# 01_detection.net
KiCad netlist of a schematic drawn in Altium Designer
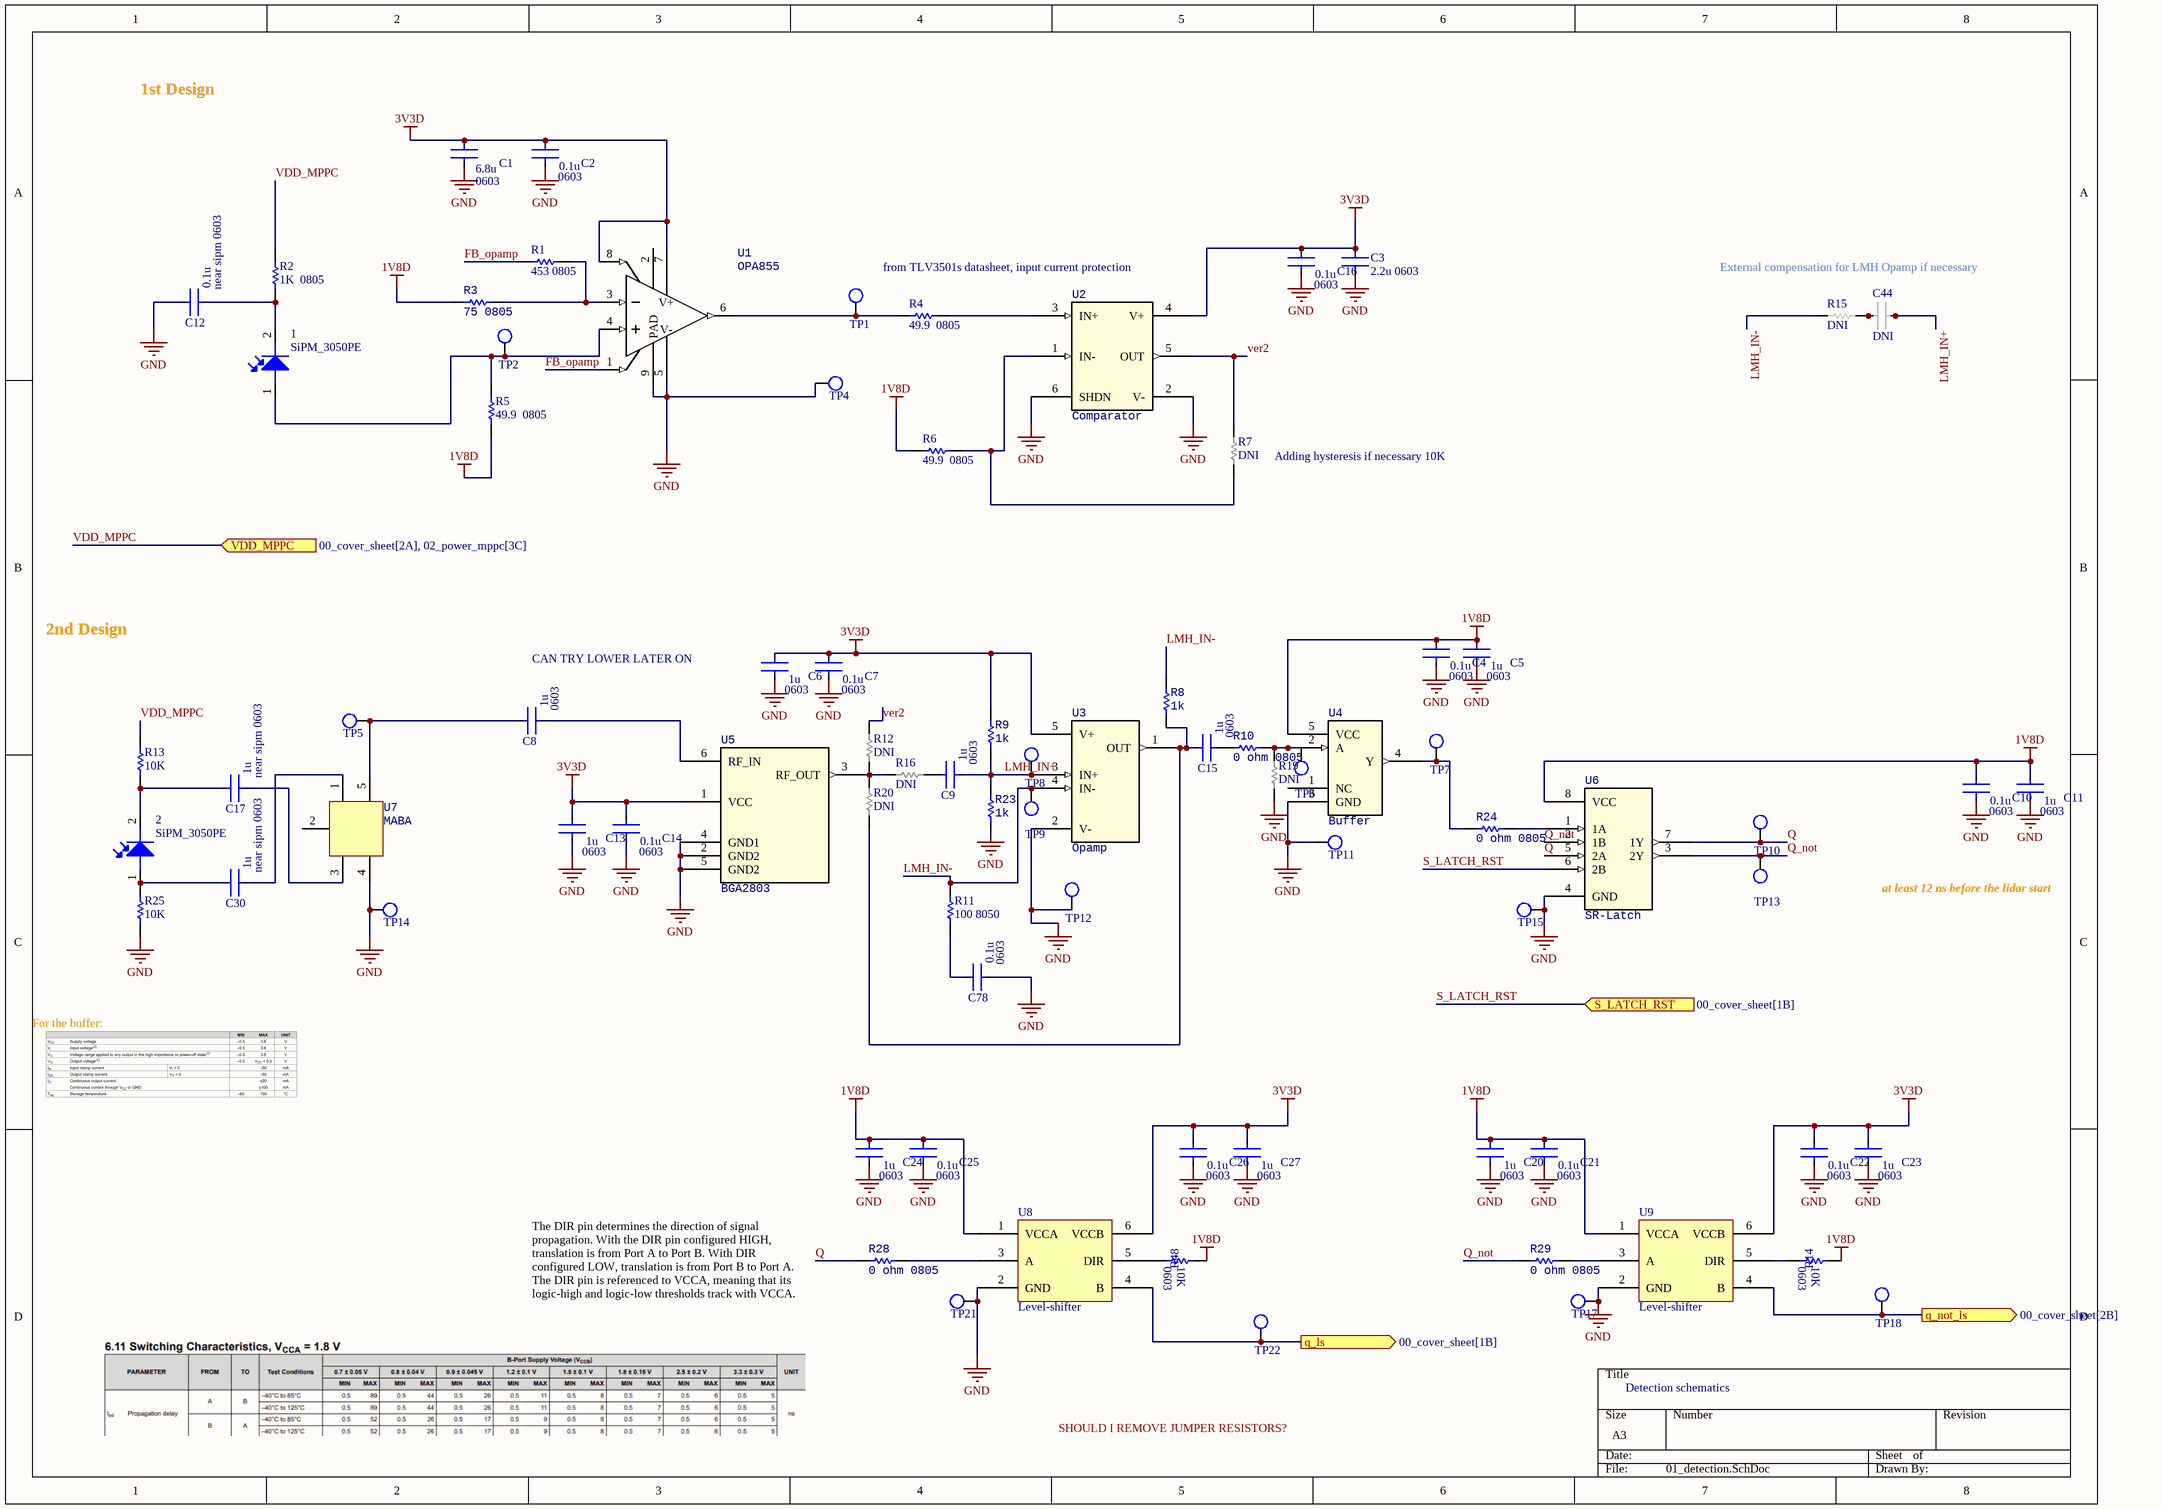
[diagram p0: 01_detection.SchDoc]

(export (version "E")
  (design (tool "Eeschema 10.0.6"))
  (components
    (comp (ref "1")
      (value "SiPM_3050PE")
      (footprint "MPPC-S13360-3050PE")
      (libsource (lib "tcspc00") (part "SiPM_3050PE"))
    )
    (comp (ref "2")
      (value "SiPM_3050PE")
      (footprint "MPPC-S13360-3050PE")
      (libsource (lib "tcspc00") (part "SiPM_3050PE"))
    )
    (comp (ref "C1")
      (value "C1608X5R1E685K080AC")
      (footprint "CAPTDK0603")
      (description "CAP CER 6.8UF 25V X5R 0603")
      (libsource (lib "tcspc00") (part "C1608X5R1E685K080AC"))
    )
    (comp (ref "C2")
      (value "CGA3E2X7R1H104K080AA")
      (footprint "CAPTDK0603")
      (description "CAP CER 0.1UF 50V X7R 0603")
      (libsource (lib "tcspc00") (part "CGA3E2X7R1H104K080AA"))
    )
    (comp (ref "C3")
      (value "2.2u 0603")
      (footprint "CAPTDK0603")
      (description "CAP CER 2.2UF 25V X5R 0603")
      (libsource (lib "tcspc00") (part "C1608X5R1E225K080AB"))
    )
    (comp (ref "C4")
      (value "CGA3E2X7R1H104K080AA")
      (footprint "CAPTDK0603")
      (description "CAP CER 0.1UF 50V X7R 0603")
      (libsource (lib "tcspc00") (part "CGA3E2X7R1H104K080AA"))
    )
    (comp (ref "C5")
      (value "C1608X5R1E105K080AC")
      (footprint "CAPTDK0603")
      (description "CAP CER 1UF 25V X5R 0603")
      (libsource (lib "tcspc00") (part "C1608X5R1E105K080AC"))
    )
    (comp (ref "C6")
      (value "C1608X5R1E105K080AC")
      (footprint "CAPTDK0603")
      (description "CAP CER 1UF 25V X5R 0603")
      (libsource (lib "tcspc00") (part "C1608X5R1E105K080AC"))
    )
    (comp (ref "C7")
      (value "CGA3E2X7R1H104K080AA")
      (footprint "CAPTDK0603")
      (description "CAP CER 0.1UF 50V X7R 0603")
      (libsource (lib "tcspc00") (part "CGA3E2X7R1H104K080AA"))
    )
    (comp (ref "C8")
      (value "C1608X5R1E105K080AC")
      (footprint "CAPTDK0603")
      (description "CAP CER 1UF 25V X5R 0603")
      (libsource (lib "tcspc00") (part "C1608X5R1E105K080AC"))
    )
    (comp (ref "C9")
      (value "C1608X5R1E105K080AC")
      (footprint "CAPTDK0603")
      (description "CAP CER 1UF 25V X5R 0603")
      (libsource (lib "tcspc00") (part "C1608X5R1E105K080AC"))
    )
    (comp (ref "C10")
      (value "CGA3E2X7R1H104K080AA")
      (footprint "CAPTDK0603")
      (description "CAP CER 0.1UF 50V X7R 0603")
      (libsource (lib "tcspc00") (part "CGA3E2X7R1H104K080AA"))
    )
    (comp (ref "C11")
      (value "C1608X5R1E105K080AC")
      (footprint "CAPTDK0603")
      (description "CAP CER 1UF 25V X5R 0603")
      (libsource (lib "tcspc00") (part "C1608X5R1E105K080AC"))
    )
    (comp (ref "C12")
      (value "CL10B104KC8NNNC")
      (footprint "CAPTDK0603")
      (description "CAP CER 0.1UF 100V X7R 0603")
      (libsource (lib "tcspc00") (part "CL10B104KC8NNNC"))
    )
    (comp (ref "C13")
      (value "C1608X5R1E105K080AC")
      (footprint "CAPTDK0603")
      (description "CAP CER 1UF 25V X5R 0603")
      (libsource (lib "tcspc00") (part "C1608X5R1E105K080AC"))
    )
    (comp (ref "C14")
      (value "CGA3E2X7R1H104K080AA")
      (footprint "CAPTDK0603")
      (description "CAP CER 0.1UF 50V X7R 0603")
      (libsource (lib "tcspc00") (part "CGA3E2X7R1H104K080AA"))
    )
    (comp (ref "C15")
      (value "C1608X5R1E105K080AC")
      (footprint "CAPTDK0603")
      (description "CAP CER 1UF 25V X5R 0603")
      (libsource (lib "tcspc00") (part "C1608X5R1E105K080AC"))
    )
    (comp (ref "C16")
      (value "CGA3E2X7R1H104K080AA")
      (footprint "CAPTDK0603")
      (description "CAP CER 0.1UF 50V X7R 0603")
      (libsource (lib "tcspc00") (part "CGA3E2X7R1H104K080AA"))
    )
    (comp (ref "C17")
      (value "GRM188D72A105KE01J")
      (footprint "CAPTDK0603")
      (description "CAP CER 1UF 100V X7T 0603")
      (libsource (lib "tcspc00") (part "GRM188D72A105KE01J"))
    )
    (comp (ref "C20")
      (value "C1608X5R1E105K080AC")
      (footprint "CAPTDK0603")
      (description "CAP CER 1UF 25V X5R 0603")
      (libsource (lib "tcspc00") (part "C1608X5R1E105K080AC"))
    )
    (comp (ref "C21")
      (value "CGA3E2X7R1H104K080AA")
      (footprint "CAPTDK0603")
      (description "CAP CER 0.1UF 50V X7R 0603")
      (libsource (lib "tcspc00") (part "CGA3E2X7R1H104K080AA"))
    )
    (comp (ref "C22")
      (value "CGA3E2X7R1H104K080AA")
      (footprint "CAPTDK0603")
      (description "CAP CER 0.1UF 50V X7R 0603")
      (libsource (lib "tcspc00") (part "CGA3E2X7R1H104K080AA"))
    )
    (comp (ref "C23")
      (value "C1608X5R1E105K080AC")
      (footprint "CAPTDK0603")
      (description "CAP CER 1UF 25V X5R 0603")
      (libsource (lib "tcspc00") (part "C1608X5R1E105K080AC"))
    )
    (comp (ref "C24")
      (value "C1608X5R1E105K080AC")
      (footprint "CAPTDK0603")
      (description "CAP CER 1UF 25V X5R 0603")
      (libsource (lib "tcspc00") (part "C1608X5R1E105K080AC"))
    )
    (comp (ref "C25")
      (value "CGA3E2X7R1H104K080AA")
      (footprint "CAPTDK0603")
      (description "CAP CER 0.1UF 50V X7R 0603")
      (libsource (lib "tcspc00") (part "CGA3E2X7R1H104K080AA"))
    )
    (comp (ref "C26")
      (value "CGA3E2X7R1H104K080AA")
      (footprint "CAPTDK0603")
      (description "CAP CER 0.1UF 50V X7R 0603")
      (libsource (lib "tcspc00") (part "CGA3E2X7R1H104K080AA"))
    )
    (comp (ref "C27")
      (value "C1608X5R1E105K080AC")
      (footprint "CAPTDK0603")
      (description "CAP CER 1UF 25V X5R 0603")
      (libsource (lib "tcspc00") (part "C1608X5R1E105K080AC"))
    )
    (comp (ref "C30")
      (value "GRM188D72A105KE01J")
      (footprint "CAPTDK0603")
      (description "CAP CER 1UF 100V X7T 0603")
      (libsource (lib "tcspc00") (part "GRM188D72A105KE01J"))
    )
    (comp (ref "C44")
      (value "DNI")
      (footprint "CAPTDK0603")
      (description "CAP PROVISION 0603")
      (libsource (lib "tcspc00") (part "C0402_PROVISION"))
    )
    (comp (ref "C78")
      (value "CGA3E2X7R1H104K080AA")
      (footprint "CAPTDK0603")
      (description "CAP CER 0.1UF 50V X7R 0603")
      (libsource (lib "tcspc00") (part "CGA3E2X7R1H104K080AA"))
    )
    (comp (ref "R1")
      (value "453 0805")
      (footprint "RES-STACK-POLE-0805")
      (description "RES 453 OHM 1% 1/4W 0805")
      (libsource (lib "tcspc00") (part "RK73H2ATTD4530F"))
    )
    (comp (ref "R2")
      (value "1K  0805")
      (footprint "RES-STACK-POLE-0805")
      (description "RES 1K OHM 1% 1/4W 0805")
      (libsource (lib "tcspc00") (part "RK73H2ATTD1001F"))
    )
    (comp (ref "R3")
      (value "75 0805")
      (footprint "RES-STACK-POLE-0805")
      (description "RES 75 OHM 1% 1/4W 0805")
      (libsource (lib "tcspc00") (part "RK73H2ATTD75R0F"))
    )
    (comp (ref "R4")
      (value "49.9  0805")
      (footprint "RES-STACK-POLE-0805")
      (description "RES 49.9 OHM 1% 1/4W 0805")
      (libsource (lib "tcspc00") (part "RK73H2ATTD49R9F"))
    )
    (comp (ref "R5")
      (value "49.9  0805")
      (footprint "RES-STACK-POLE-0805")
      (description "RES 49.9 OHM 1% 1/4W 0805")
      (libsource (lib "tcspc00") (part "RK73H2ATTD49R9F"))
    )
    (comp (ref "R6")
      (value "49.9  0805")
      (footprint "RES-STACK-POLE-0805")
      (description "RES 49.9 OHM 1% 1/4W 0805")
      (libsource (lib "tcspc00") (part "RK73H2ATTD49R9F"))
    )
    (comp (ref "R7")
      (value "DNI")
      (footprint "RES-STACK-POLE-0805")
      (description "RES DNI 0805")
      (libsource (lib "tcspc00") (part "R0805"))
    )
    (comp (ref "R8")
      (value "1k")
      (footprint "RES_0603")
      (description "RES 1K OHM 1% 1/10W 0603")
      (fields
        (field (name "MANUFACTURER") "Stackpole Electronics")
        (field (name "MANUFACTURER PART NUMBER") "RMCF0603FT1K00")
      )
      (libsource (lib "tcspc00") (part "RMCF0603FT1K00"))
    )
    (comp (ref "R9")
      (value "1k")
      (footprint "RES_0603")
      (description "RES 1K OHM 1% 1/10W 0603")
      (fields
        (field (name "MANUFACTURER") "Stackpole Electronics")
        (field (name "MANUFACTURER PART NUMBER") "RMCF0603FT1K00")
      )
      (libsource (lib "tcspc00") (part "RMCF0603FT1K00"))
    )
    (comp (ref "R10")
      (value "0 ohm 0805")
      (footprint "RES-STACK-POLE-0805")
      (description "RES 0 OHM JUMPER 1/8W 0805")
      (libsource (lib "tcspc00") (part "RC0805JR-070RL"))
    )
    (comp (ref "R11")
      (value "100 8050")
      (footprint "RES-STACK-POLE-0805")
      (description "RK73H2ATK001KIT %1 tolerance 100 ohm resistor 8050 package")
      (libsource (lib "tcspc00") (part "RK73H2AT1000F"))
    )
    (comp (ref "R12")
      (value "DNI")
      (footprint "RES-STACK-POLE-0805")
      (description "RES DNI 0805")
      (libsource (lib "tcspc00") (part "R0805"))
    )
    (comp (ref "R13")
      (value "10K")
      (footprint "RES-STACK-POLE-0805")
      (description "RES 10K OHM 1% 1/4W 0805")
      (libsource (lib "tcspc00") (part "RK73H2ATTD1002F"))
    )
    (comp (ref "R14")
      (value "RMCF0603JG10K0")
      (footprint "RES-STACK-POLE-0603")
      (description "RES 10K OHM 5% 1/10W 0603")
      (libsource (lib "tcspc00") (part "RMCF0603JG10K0"))
    )
    (comp (ref "R15")
      (value "DNI")
      (footprint "RES_0603")
      (description "RES DNI 0603")
      (libsource (lib "tcspc00") (part "R0603"))
    )
    (comp (ref "R16")
      (value "DNI")
      (footprint "RES-STACK-POLE-0805")
      (description "RES DNI 0805")
      (libsource (lib "tcspc00") (part "R0805"))
    )
    (comp (ref "R19")
      (value "DNI")
      (footprint "RES-STACK-POLE-0805")
      (description "RES DNI 0805")
      (libsource (lib "tcspc00") (part "R0805"))
    )
    (comp (ref "R20")
      (value "DNI")
      (footprint "RES-STACK-POLE-0805")
      (description "RES DNI 0805")
      (libsource (lib "tcspc00") (part "R0805"))
    )
    (comp (ref "R23")
      (value "1k")
      (footprint "RES_0603")
      (description "RES 1K OHM 1% 1/10W 0603")
      (fields
        (field (name "MANUFACTURER") "Stackpole Electronics")
        (field (name "MANUFACTURER PART NUMBER") "RMCF0603FT1K00")
      )
      (libsource (lib "tcspc00") (part "RMCF0603FT1K00"))
    )
    (comp (ref "R24")
      (value "0 ohm 0805")
      (footprint "RES-STACK-POLE-0805")
      (description "RES 0 OHM JUMPER 1/8W 0805")
      (libsource (lib "tcspc00") (part "RC0805JR-070RL"))
    )
    (comp (ref "R25")
      (value "10K")
      (footprint "RES-STACK-POLE-0805")
      (description "RES 10K OHM 1% 1/4W 0805")
      (libsource (lib "tcspc00") (part "RK73H2ATTD1002F"))
    )
    (comp (ref "R28")
      (value "0 ohm 0805")
      (footprint "RES-STACK-POLE-0805")
      (description "RES 0 OHM JUMPER 1/8W 0805")
      (libsource (lib "tcspc00") (part "RC0805JR-070RL"))
    )
    (comp (ref "R29")
      (value "0 ohm 0805")
      (footprint "RES-STACK-POLE-0805")
      (description "RES 0 OHM JUMPER 1/8W 0805")
      (libsource (lib "tcspc00") (part "RC0805JR-070RL"))
    )
    (comp (ref "R48")
      (value "RMCF0603JG10K0")
      (footprint "RES-STACK-POLE-0603")
      (description "RES 10K OHM 5% 1/10W 0603")
      (libsource (lib "tcspc00") (part "RMCF0603JG10K0"))
    )
    (comp (ref "TP1")
      (value "TESTPOINT_S")
      (footprint "TESTPOINT_S")
      (description "Testpoint Surface Pad")
      (libsource (lib "tcspc00") (part "TESTPOINT_S"))
    )
    (comp (ref "TP2")
      (value "TESTPOINT_S")
      (footprint "TESTPOINT_S")
      (description "Testpoint Surface Pad")
      (libsource (lib "tcspc00") (part "TESTPOINT_S"))
    )
    (comp (ref "TP4")
      (value "TESTPOINT_S")
      (footprint "TESTPOINT_S")
      (description "Testpoint Surface Pad")
      (libsource (lib "tcspc00") (part "TESTPOINT_S"))
    )
    (comp (ref "TP5")
      (value "TESTPOINT_S")
      (footprint "TESTPOINT_S")
      (description "Testpoint Surface Pad")
      (libsource (lib "tcspc00") (part "TESTPOINT_S"))
    )
    (comp (ref "TP6")
      (value "TESTPOINT_S")
      (footprint "TESTPOINT_S")
      (description "Testpoint Surface Pad")
      (libsource (lib "tcspc00") (part "TESTPOINT_S"))
    )
    (comp (ref "TP7")
      (value "TESTPOINT_S")
      (footprint "TESTPOINT_S")
      (description "Testpoint Surface Pad")
      (libsource (lib "tcspc00") (part "TESTPOINT_S"))
    )
    (comp (ref "TP8")
      (value "TESTPOINT_S")
      (footprint "TESTPOINT_S")
      (description "Testpoint Surface Pad")
      (libsource (lib "tcspc00") (part "TESTPOINT_S"))
    )
    (comp (ref "TP9")
      (value "TESTPOINT_S")
      (footprint "TESTPOINT_S")
      (description "Testpoint Surface Pad")
      (libsource (lib "tcspc00") (part "TESTPOINT_S"))
    )
    (comp (ref "TP10")
      (value "TESTPOINT_S")
      (footprint "TESTPOINT_S")
      (description "Testpoint Surface Pad")
      (libsource (lib "tcspc00") (part "TESTPOINT_S"))
    )
    (comp (ref "TP11")
      (value "TESTPOINT_S")
      (footprint "TESTPOINT_S")
      (description "Testpoint Surface Pad")
      (libsource (lib "tcspc00") (part "TESTPOINT_S"))
    )
    (comp (ref "TP12")
      (value "TESTPOINT_S")
      (footprint "TESTPOINT_S")
      (description "Testpoint Surface Pad")
      (libsource (lib "tcspc00") (part "TESTPOINT_S"))
    )
    (comp (ref "TP13")
      (value "TESTPOINT_S")
      (footprint "TESTPOINT_S")
      (description "Testpoint Surface Pad")
      (libsource (lib "tcspc00") (part "TESTPOINT_S"))
    )
    (comp (ref "TP14")
      (value "TESTPOINT_S")
      (footprint "TESTPOINT_S")
      (description "Testpoint Surface Pad")
      (libsource (lib "tcspc00") (part "TESTPOINT_S"))
    )
    (comp (ref "TP15")
      (value "TESTPOINT_S")
      (footprint "TESTPOINT_S")
      (description "Testpoint Surface Pad")
      (libsource (lib "tcspc00") (part "TESTPOINT_S"))
    )
    (comp (ref "TP17")
      (value "TESTPOINT_S")
      (footprint "TESTPOINT_S")
      (description "Testpoint Surface Pad")
      (libsource (lib "tcspc00") (part "TESTPOINT_S"))
    )
    (comp (ref "TP18")
      (value "TESTPOINT_S")
      (footprint "TESTPOINT_S")
      (description "Testpoint Surface Pad")
      (libsource (lib "tcspc00") (part "TESTPOINT_S"))
    )
    (comp (ref "TP21")
      (value "TESTPOINT_S")
      (footprint "TESTPOINT_S")
      (description "Testpoint Surface Pad")
      (libsource (lib "tcspc00") (part "TESTPOINT_S"))
    )
    (comp (ref "TP22")
      (value "TESTPOINT_S")
      (footprint "TESTPOINT_S")
      (description "Testpoint Surface Pad")
      (libsource (lib "tcspc00") (part "TESTPOINT_S"))
    )
    (comp (ref "U1")
      (value "OPA855")
      (footprint "WSON-08")
      (description "IC OPAMP GP 1 CIRCUIT 8WSON")
      (libsource (lib "tcspc00") (part "OPA855"))
    )
    (comp (ref "U2")
      (value "Comparator")
      (footprint "SOT-23")
      (description "IC COMPARATOR 1 GEN PUR SOT23-6")
      (libsource (lib "tcspc00") (part "TLV35011AIDBVT"))
    )
    (comp (ref "U3")
      (value "Opamp")
      (footprint "MF05A-L")
      (description "IC OPAMP VFB 1 CIRCUIT SOT23-5")
      (libsource (lib "tcspc00") (part "LMH6629MFE/NOPB"))
    )
    (comp (ref "U4")
      (value "Buffer")
      (footprint "DBV0005A")
      (description "IC BUF NON-INVERT 2.7V SOT23-5")
      (libsource (lib "tcspc00") (part "SN74AUC1G17DBVR"))
    )
    (comp (ref "U5")
      (value "BGA2803")
      (footprint "SOT_02,115_NXP-M")
      (description "IC RF AMP GPS 0HZ-2.2GHZ 6TSSOP")
      (libsource (lib "tcspc00") (part "BGA2803"))
    )
    (comp (ref "U6")
      (value "SR-Latch")
      (footprint "DCU0008A")
      (description "2-ch, 2-input, 0.8-V to 2.7-V high speed NOR gates")
      (libsource (lib "tcspc00") (part "SN74AUC2G02DCUR"))
    )
    (comp (ref "U7")
      (value "MABA")
      (footprint "MABA-007159-")
      (description "BALUN 4.5MHZ-3GHZ 1:1 6SMD FLAT")
      (libsource (lib "tcspc00") (part "MABA-007159"))
    )
    (comp (ref "U8")
      (value "Level-shifter")
      (footprint "SON50P100X60-6N")
      (description "IC TRANSLTR BIDIRECTIONAL 6SON SN74AXCH1T45DRY2 texas instruments")
      (libsource (lib "tcspc00") (part "SN74AXCH1T45DRY2"))
    )
    (comp (ref "U9")
      (value "Level-shifter")
      (footprint "SON50P100X60-6N")
      (description "IC TRANSLTR BIDIRECTIONAL 6SON SN74AXCH1T45DRY2 texas instruments")
      (libsource (lib "tcspc00") (part "SN74AXCH1T45DRY2"))
    )
  )
  (nets
    (net (code "1") (name "/FB_opamp") (class "Default")
      (node (ref "R1") (pin "1") (pinfunction "1_1") (pintype "passive"))
      (node (ref "U1") (pin "1") (pinfunction "FB_1") (pintype "input"))
    )
    (net (code "2") (name "/LMH_IN+") (class "Default")
      (node (ref "C44") (pin "2") (pinfunction "2_2") (pintype "passive"))
      (node (ref "C9") (pin "2") (pinfunction "2_2") (pintype "passive"))
      (node (ref "R23") (pin "2") (pinfunction "2_2") (pintype "passive"))
      (node (ref "R9") (pin "1") (pinfunction "1_1") (pintype "passive"))
      (node (ref "TP8") (pin "1") (pinfunction "1_1") (pintype "passive"))
      (node (ref "U3") (pin "3") (pinfunction "IN+_3") (pintype "input"))
    )
    (net (code "3") (name "/LMH_IN-") (class "Default")
      (node (ref "R11") (pin "2") (pinfunction "2_2") (pintype "passive"))
      (node (ref "R15") (pin "1") (pinfunction "1_1") (pintype "passive"))
      (node (ref "R8") (pin "2") (pinfunction "2_2") (pintype "passive"))
      (node (ref "TP9") (pin "1") (pinfunction "1_1") (pintype "passive"))
      (node (ref "U3") (pin "4") (pinfunction "IN-_4") (pintype "input"))
    )
    (net (code "4") (name "/Q") (class "Default")
      (node (ref "R28") (pin "1") (pinfunction "1_1") (pintype "passive"))
      (node (ref "TP10") (pin "1") (pinfunction "1_1") (pintype "passive"))
      (node (ref "U6") (pin "5") (pinfunction "2A_5") (pintype "input"))
      (node (ref "U6") (pin "7") (pinfunction "1Y_7") (pintype "output"))
    )
    (net (code "5") (name "/Q_not") (class "Default")
      (node (ref "R29") (pin "1") (pinfunction "1_1") (pintype "passive"))
      (node (ref "TP13") (pin "1") (pinfunction "1_1") (pintype "passive"))
      (node (ref "U6") (pin "2") (pinfunction "1B_2") (pintype "input"))
      (node (ref "U6") (pin "3") (pinfunction "2Y_3") (pintype "output"))
    )
    (net (code "6") (name "/S_LATCH_RST") (class "Default")
      (node (ref "U6") (pin "6") (pinfunction "2B_6") (pintype "input"))
    )
    (net (code "7") (name "/VDD_MPPC") (class "Default")
      (node (ref "R13") (pin "2") (pinfunction "2_2") (pintype "passive"))
      (node (ref "R2") (pin "2") (pinfunction "2_2") (pintype "passive"))
    )
    (net (code "8") (name "/q_ls") (class "Default")
      (node (ref "TP22") (pin "1") (pinfunction "1_1") (pintype "passive"))
      (node (ref "U8") (pin "4") (pinfunction "B_4") (pintype "passive"))
    )
    (net (code "9") (name "/q_not_ls") (class "Default")
      (node (ref "TP18") (pin "1") (pinfunction "1_1") (pintype "passive"))
      (node (ref "U9") (pin "4") (pinfunction "B_4") (pintype "passive"))
    )
    (net (code "10") (name "/ver2") (class "Default")
      (node (ref "R12") (pin "2") (pinfunction "2_2") (pintype "passive"))
      (node (ref "R7") (pin "2") (pinfunction "2_2") (pintype "passive"))
      (node (ref "U2") (pin "5") (pinfunction "OUT_5") (pintype "output"))
    )
    (net (code "11") (name "1V8D") (class "Default")
      (node (ref "C10") (pin "1") (pinfunction "1_1") (pintype "passive"))
      (node (ref "C11") (pin "1") (pinfunction "1_1") (pintype "passive"))
      (node (ref "C20") (pin "1") (pinfunction "1_1") (pintype "passive"))
      (node (ref "C21") (pin "1") (pinfunction "1_1") (pintype "passive"))
      (node (ref "C24") (pin "1") (pinfunction "1_1") (pintype "passive"))
      (node (ref "C25") (pin "1") (pinfunction "1_1") (pintype "passive"))
      (node (ref "C4") (pin "1") (pinfunction "1_1") (pintype "passive"))
      (node (ref "C5") (pin "1") (pinfunction "1_1") (pintype "passive"))
      (node (ref "R14") (pin "2") (pinfunction "2_2") (pintype "passive"))
      (node (ref "R3") (pin "1") (pinfunction "1_1") (pintype "passive"))
      (node (ref "R48") (pin "2") (pinfunction "2_2") (pintype "passive"))
      (node (ref "R5") (pin "1") (pinfunction "1_1") (pintype "passive"))
      (node (ref "R6") (pin "1") (pinfunction "1_1") (pintype "passive"))
      (node (ref "U4") (pin "5") (pinfunction "VCC_5") (pintype "power_in"))
      (node (ref "U6") (pin "8") (pinfunction "VCC_8") (pintype "power_in"))
      (node (ref "U8") (pin "1") (pinfunction "VCCA_1") (pintype "passive"))
      (node (ref "U9") (pin "1") (pinfunction "VCCA_1") (pintype "passive"))
    )
    (net (code "12") (name "3V3D") (class "Default")
      (node (ref "C1") (pin "1") (pinfunction "1_1") (pintype "passive"))
      (node (ref "C13") (pin "1") (pinfunction "1_1") (pintype "passive"))
      (node (ref "C14") (pin "1") (pinfunction "1_1") (pintype "passive"))
      (node (ref "C16") (pin "1") (pinfunction "1_1") (pintype "passive"))
      (node (ref "C2") (pin "1") (pinfunction "1_1") (pintype "passive"))
      (node (ref "C22") (pin "1") (pinfunction "1_1") (pintype "passive"))
      (node (ref "C23") (pin "1") (pinfunction "1_1") (pintype "passive"))
      (node (ref "C26") (pin "1") (pinfunction "1_1") (pintype "passive"))
      (node (ref "C27") (pin "1") (pinfunction "1_1") (pintype "passive"))
      (node (ref "C3") (pin "1") (pinfunction "1_1") (pintype "passive"))
      (node (ref "C6") (pin "1") (pinfunction "1_1") (pintype "passive"))
      (node (ref "C7") (pin "1") (pinfunction "1_1") (pintype "passive"))
      (node (ref "R9") (pin "2") (pinfunction "2_2") (pintype "passive"))
      (node (ref "U1") (pin "7") (pinfunction "VS+_7") (pintype "power_in"))
      (node (ref "U1") (pin "8") (pinfunction "PD_N_8") (pintype "input"))
      (node (ref "U2") (pin "4") (pinfunction "V+_4") (pintype "power_in"))
      (node (ref "U3") (pin "5") (pinfunction "V+_5") (pintype "power_in"))
      (node (ref "U5") (pin "1") (pinfunction "VCC_1") (pintype "power_in"))
      (node (ref "U8") (pin "6") (pinfunction "VCCB_6") (pintype "passive"))
      (node (ref "U9") (pin "6") (pinfunction "VCCB_6") (pintype "passive"))
    )
    (net (code "13") (name "GND") (class "Default")
      (node (ref "C1") (pin "2") (pinfunction "2_2") (pintype "passive"))
      (node (ref "C10") (pin "2") (pinfunction "2_2") (pintype "passive"))
      (node (ref "C11") (pin "2") (pinfunction "2_2") (pintype "passive"))
      (node (ref "C12") (pin "1") (pinfunction "1_1") (pintype "passive"))
      (node (ref "C13") (pin "2") (pinfunction "2_2") (pintype "passive"))
      (node (ref "C14") (pin "2") (pinfunction "2_2") (pintype "passive"))
      (node (ref "C16") (pin "2") (pinfunction "2_2") (pintype "passive"))
      (node (ref "C2") (pin "2") (pinfunction "2_2") (pintype "passive"))
      (node (ref "C20") (pin "2") (pinfunction "2_2") (pintype "passive"))
      (node (ref "C21") (pin "2") (pinfunction "2_2") (pintype "passive"))
      (node (ref "C22") (pin "2") (pinfunction "2_2") (pintype "passive"))
      (node (ref "C23") (pin "2") (pinfunction "2_2") (pintype "passive"))
      (node (ref "C24") (pin "2") (pinfunction "2_2") (pintype "passive"))
      (node (ref "C25") (pin "2") (pinfunction "2_2") (pintype "passive"))
      (node (ref "C26") (pin "2") (pinfunction "2_2") (pintype "passive"))
      (node (ref "C27") (pin "2") (pinfunction "2_2") (pintype "passive"))
      (node (ref "C3") (pin "2") (pinfunction "2_2") (pintype "passive"))
      (node (ref "C4") (pin "2") (pinfunction "2_2") (pintype "passive"))
      (node (ref "C5") (pin "2") (pinfunction "2_2") (pintype "passive"))
      (node (ref "C6") (pin "2") (pinfunction "2_2") (pintype "passive"))
      (node (ref "C7") (pin "2") (pinfunction "2_2") (pintype "passive"))
      (node (ref "C78") (pin "2") (pinfunction "2_2") (pintype "passive"))
      (node (ref "R19") (pin "1") (pinfunction "1_1") (pintype "passive"))
      (node (ref "R23") (pin "1") (pinfunction "1_1") (pintype "passive"))
      (node (ref "R25") (pin "1") (pinfunction "1_1") (pintype "passive"))
      (node (ref "TP11") (pin "1") (pinfunction "1_1") (pintype "passive"))
      (node (ref "TP12") (pin "1") (pinfunction "1_1") (pintype "passive"))
      (node (ref "TP14") (pin "1") (pinfunction "1_1") (pintype "passive"))
      (node (ref "TP15") (pin "1") (pinfunction "1_1") (pintype "passive"))
      (node (ref "TP17") (pin "1") (pinfunction "1_1") (pintype "passive"))
      (node (ref "TP21") (pin "1") (pinfunction "1_1") (pintype "passive"))
      (node (ref "TP4") (pin "1") (pinfunction "1_1") (pintype "passive"))
      (node (ref "U1") (pin "5") (pinfunction "VS-_5") (pintype "power_in"))
      (node (ref "U1") (pin "9") (pinfunction "PAD_9") (pintype "power_in"))
      (node (ref "U2") (pin "2") (pinfunction "V-_2") (pintype "power_in"))
      (node (ref "U2") (pin "6") (pinfunction "SHDN_6") (pintype "passive"))
      (node (ref "U3") (pin "2") (pinfunction "V-_2") (pintype "power_in"))
      (node (ref "U4") (pin "3") (pinfunction "GND_3") (pintype "power_in"))
      (node (ref "U5") (pin "2") (pinfunction "GND2_2") (pintype "power_in"))
      (node (ref "U5") (pin "4") (pinfunction "GND1_4") (pintype "power_in"))
      (node (ref "U5") (pin "5") (pinfunction "GND2_5") (pintype "power_in"))
      (node (ref "U6") (pin "4") (pinfunction "GND_4") (pintype "power_in"))
      (node (ref "U7") (pin "4") (pinfunction "4_4") (pintype "passive"))
      (node (ref "U8") (pin "2") (pinfunction "GND_2") (pintype "passive"))
      (node (ref "U9") (pin "2") (pinfunction "GND_2") (pintype "passive"))
    )
    (net (code "14") (name "Net-(1-Pad2)") (class "Default")
      (node (ref "1") (pin "2") (pinfunction "2_2") (pintype "passive"))
      (node (ref "C12") (pin "2") (pinfunction "2_2") (pintype "passive"))
      (node (ref "R2") (pin "1") (pinfunction "1_1") (pintype "passive"))
    )
    (net (code "15") (name "Net-(2-Pad1)") (class "Default")
      (node (ref "2") (pin "1") (pinfunction "1_1") (pintype "passive"))
      (node (ref "C30") (pin "1") (pinfunction "1_1") (pintype "passive"))
      (node (ref "R25") (pin "2") (pinfunction "2_2") (pintype "passive"))
    )
    (net (code "16") (name "Net-(2-Pad2)") (class "Default")
      (node (ref "2") (pin "2") (pinfunction "2_2") (pintype "passive"))
      (node (ref "C17") (pin "1") (pinfunction "1_1") (pintype "passive"))
      (node (ref "R13") (pin "1") (pinfunction "1_1") (pintype "passive"))
    )
    (net (code "17") (name "Net-(C8-Pad1)") (class "Default")
      (node (ref "C8") (pin "1") (pinfunction "1_1") (pintype "passive"))
      (node (ref "TP5") (pin "1") (pinfunction "1_1") (pintype "passive"))
      (node (ref "U7") (pin "5") (pinfunction "5_5") (pintype "passive"))
    )
    (net (code "18") (name "Net-(C9-Pad1)") (class "Default")
      (node (ref "C9") (pin "1") (pinfunction "1_1") (pintype "passive"))
      (node (ref "R16") (pin "2") (pinfunction "2_2") (pintype "passive"))
    )
    (net (code "19") (name "Net-(C15-Pad2)") (class "Default")
      (node (ref "C15") (pin "2") (pinfunction "2_2") (pintype "passive"))
      (node (ref "R10") (pin "1") (pinfunction "1_1") (pintype "passive"))
    )
    (net (code "20") (name "Net-(C17-Pad2)") (class "Default")
      (node (ref "C17") (pin "2") (pinfunction "2_2") (pintype "passive"))
      (node (ref "U7") (pin "3") (pinfunction "3_3") (pintype "passive"))
    )
    (net (code "21") (name "Net-(C30-Pad2)") (class "Default")
      (node (ref "C30") (pin "2") (pinfunction "2_2") (pintype "passive"))
      (node (ref "U7") (pin "1") (pinfunction "1_1") (pintype "passive"))
    )
    (net (code "22") (name "Net-(C44-Pad1)") (class "Default")
      (node (ref "C44") (pin "1") (pinfunction "1_1") (pintype "passive"))
      (node (ref "R15") (pin "2") (pinfunction "2_2") (pintype "passive"))
    )
    (net (code "23") (name "Net-(C78-Pad1)") (class "Default")
      (node (ref "C78") (pin "1") (pinfunction "1_1") (pintype "passive"))
      (node (ref "R11") (pin "1") (pinfunction "1_1") (pintype "passive"))
    )
    (net (code "24") (name "Net-(U1-IN+)") (class "Default")
      (node (ref "1") (pin "1") (pinfunction "1_1") (pintype "passive"))
      (node (ref "R5") (pin "2") (pinfunction "2_2") (pintype "passive"))
      (node (ref "TP2") (pin "1") (pinfunction "1_1") (pintype "passive"))
      (node (ref "U1") (pin "4") (pinfunction "IN+_4") (pintype "input"))
    )
    (net (code "25") (name "Net-(U1-IN-)") (class "Default")
      (node (ref "R1") (pin "2") (pinfunction "2_2") (pintype "passive"))
      (node (ref "R3") (pin "2") (pinfunction "2_2") (pintype "passive"))
      (node (ref "U1") (pin "3") (pinfunction "IN-_3") (pintype "input"))
    )
    (net (code "26") (name "Net-(U1-OUT)") (class "Default")
      (node (ref "R4") (pin "1") (pinfunction "1_1") (pintype "passive"))
      (node (ref "TP1") (pin "1") (pinfunction "1_1") (pintype "passive"))
      (node (ref "U1") (pin "6") (pinfunction "OUT_6") (pintype "output"))
    )
    (net (code "27") (name "Net-(U2-IN+)") (class "Default")
      (node (ref "R4") (pin "2") (pinfunction "2_2") (pintype "passive"))
      (node (ref "U2") (pin "3") (pinfunction "IN+_3") (pintype "input"))
    )
    (net (code "28") (name "Net-(U2-IN-)") (class "Default")
      (node (ref "R6") (pin "2") (pinfunction "2_2") (pintype "passive"))
      (node (ref "R7") (pin "1") (pinfunction "1_1") (pintype "passive"))
      (node (ref "U2") (pin "1") (pinfunction "IN-_1") (pintype "input"))
    )
    (net (code "29") (name "Net-(U3-OUT)") (class "Default")
      (node (ref "C15") (pin "1") (pinfunction "1_1") (pintype "passive"))
      (node (ref "R20") (pin "1") (pinfunction "1_1") (pintype "passive"))
      (node (ref "R8") (pin "1") (pinfunction "1_1") (pintype "passive"))
      (node (ref "U3") (pin "1") (pinfunction "OUT_1") (pintype "output"))
    )
    (net (code "30") (name "Net-(U4-A)") (class "Default")
      (node (ref "R10") (pin "2") (pinfunction "2_2") (pintype "passive"))
      (node (ref "R19") (pin "2") (pinfunction "2_2") (pintype "passive"))
      (node (ref "TP6") (pin "1") (pinfunction "1_1") (pintype "passive"))
      (node (ref "U4") (pin "2") (pinfunction "A_2") (pintype "input"))
    )
    (net (code "31") (name "Net-(U4-Y)") (class "Default")
      (node (ref "R24") (pin "1") (pinfunction "1_1") (pintype "passive"))
      (node (ref "TP7") (pin "1") (pinfunction "1_1") (pintype "passive"))
      (node (ref "U4") (pin "4") (pinfunction "Y_4") (pintype "output"))
    )
    (net (code "32") (name "Net-(U5-RF_IN)") (class "Default")
      (node (ref "C8") (pin "2") (pinfunction "2_2") (pintype "passive"))
      (node (ref "U5") (pin "6") (pinfunction "RF_IN_6") (pintype "passive"))
    )
    (net (code "33") (name "Net-(U5-RF_OUT)") (class "Default")
      (node (ref "R12") (pin "1") (pinfunction "1_1") (pintype "passive"))
      (node (ref "R16") (pin "1") (pinfunction "1_1") (pintype "passive"))
      (node (ref "R20") (pin "2") (pinfunction "2_2") (pintype "passive"))
      (node (ref "U5") (pin "3") (pinfunction "RF_OUT_3") (pintype "output"))
    )
    (net (code "34") (name "Net-(U6-1A)") (class "Default")
      (node (ref "R24") (pin "2") (pinfunction "2_2") (pintype "passive"))
      (node (ref "U6") (pin "1") (pinfunction "1A_1") (pintype "input"))
    )
    (net (code "35") (name "Net-(U8-A)") (class "Default")
      (node (ref "R28") (pin "2") (pinfunction "2_2") (pintype "passive"))
      (node (ref "U8") (pin "3") (pinfunction "A_3") (pintype "passive"))
    )
    (net (code "36") (name "Net-(U8-DIR)") (class "Default")
      (node (ref "R48") (pin "1") (pinfunction "1_1") (pintype "passive"))
      (node (ref "U8") (pin "5") (pinfunction "DIR_5") (pintype "passive"))
    )
    (net (code "37") (name "Net-(U9-A)") (class "Default")
      (node (ref "R29") (pin "2") (pinfunction "2_2") (pintype "passive"))
      (node (ref "U9") (pin "3") (pinfunction "A_3") (pintype "passive"))
    )
    (net (code "38") (name "Net-(U9-DIR)") (class "Default")
      (node (ref "R14") (pin "1") (pinfunction "1_1") (pintype "passive"))
      (node (ref "U9") (pin "5") (pinfunction "DIR_5") (pintype "passive"))
    )
    (net (code "39") (name "unconnected-(U1-NC-Pad2)") (class "Default")
      (node (ref "U1") (pin "2") (pinfunction "NC_2") (pintype "passive"))
    )
    (net (code "40") (name "unconnected-(U4-NC-Pad1)") (class "Default")
      (node (ref "U4") (pin "1") (pinfunction "NC_1") (pintype "passive"))
    )
    (net (code "41") (name "unconnected-(U7-Pad2)") (class "Default")
      (node (ref "U7") (pin "2") (pinfunction "2_2") (pintype "passive"))
    )
  )
)
